# ultra-violet-tooth-sensor-mk-2_0.net
KiCad netlist of a schematic drawn in EAGLE
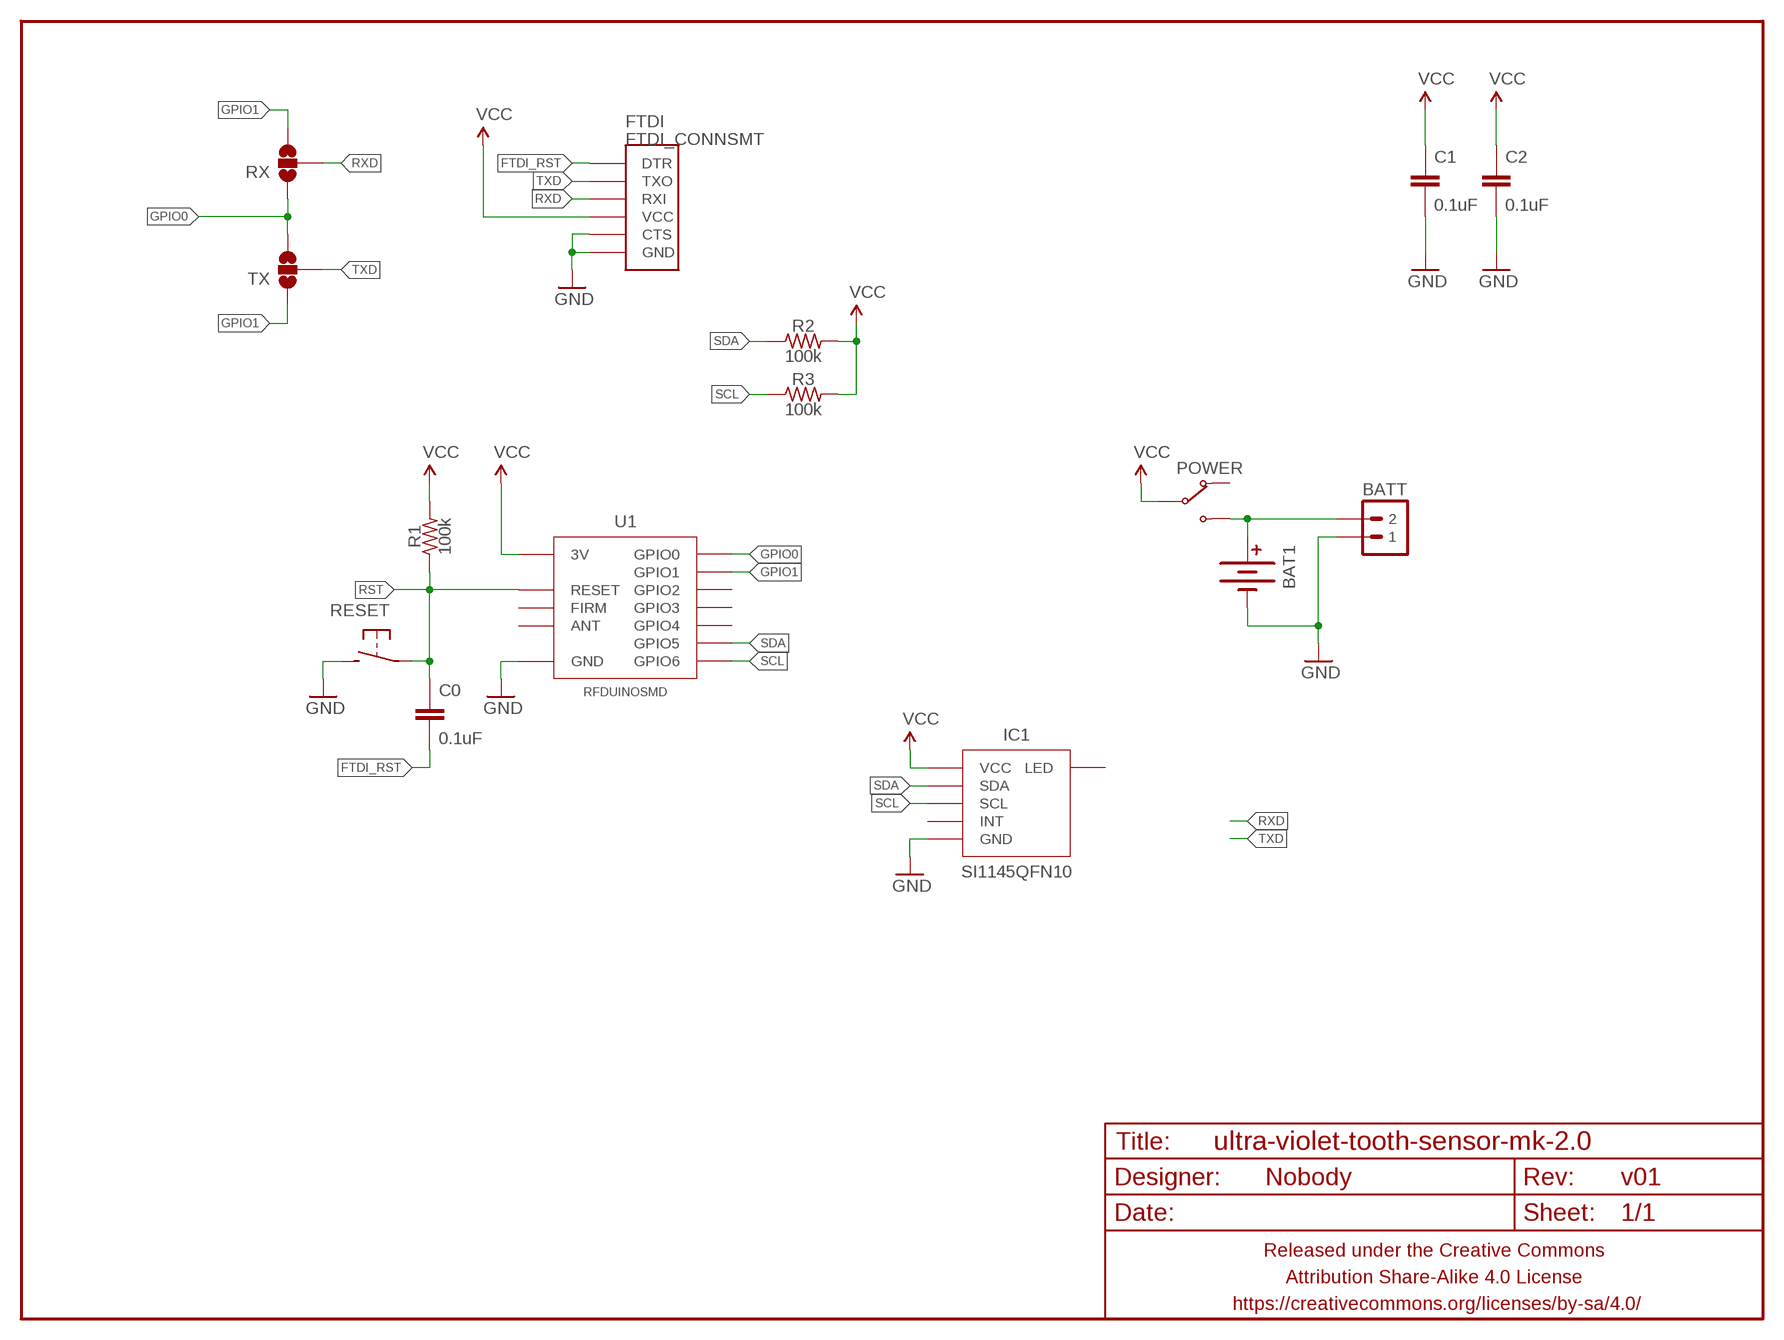
[diagram p0: schematic, sheet 1]

(export (version "E")
  (design (tool "Eeschema 10.0.6"))
  (components
    (comp (ref "BAT1")
      (value "BATTERY20MMSMD-MINE")
      (footprint "eagle-import:BATTCON_20MM_MINE")
      (libsource (lib "eagle-import") (part "BATTERY20MMSMD-MINE"))
    )
    (comp (ref "BATT")
      (value "M02PTH-CENTERED-R+")
      (footprint "eagle-import:1X02-CENTER-R+")
      (libsource (lib "eagle-import") (part "M02PTH-CENTERED-R+"))
    )
    (comp (ref "C0")
      (value "0.1uF")
      (footprint "eagle-import:C0805")
      (libsource (lib "eagle-import") (part "CAPACITOR-CERAMICC0805"))
    )
    (comp (ref "C1")
      (value "0.1uF")
      (footprint "eagle-import:C0805")
      (libsource (lib "eagle-import") (part "CAPACITOR-CERAMICC0805"))
    )
    (comp (ref "C2")
      (value "0.1uF")
      (footprint "eagle-import:C0805")
      (libsource (lib "eagle-import") (part "CAPACITOR-CERAMICC0805"))
    )
    (comp (ref "FRAME1")
      (value "FRAME-LETTERNO_PACKAGE")
      (footprint "eagle-import:DUMMY")
      (fields (field (name "DESIGNER") "Nobody"))
      (libsource (lib "eagle-import") (part "FRAME-LETTERNO_PACKAGE"))
    )
    (comp (ref "FTDI")
      (value "FTDI_CONNSMT")
      (footprint "eagle-import:FTDI_CONN_SMT")
      (libsource (lib "eagle-import") (part "FTDI_CONNSMT"))
    )
    (comp (ref "IC1")
      (value "SI1145QFN10")
      (footprint "eagle-import:SI1145")
      (libsource (lib "eagle-import") (part "SI1145QFN10"))
    )
    (comp (ref "POWER")
      (value "SWITCH-SPDTSMD-RA")
      (footprint "eagle-import:SWITCH-SPDT-SMD-RA")
      (libsource (lib "eagle-import") (part "SWITCH-SPDTSMD-RA"))
    )
    (comp (ref "R1")
      (value "100k")
      (footprint "eagle-import:R0805")
      (libsource (lib "eagle-import") (part "RESISTORR0805"))
    )
    (comp (ref "R2")
      (value "100k")
      (footprint "eagle-import:R0805")
      (libsource (lib "eagle-import") (part "RESISTORR0805"))
    )
    (comp (ref "R3")
      (value "100k")
      (footprint "eagle-import:R0805")
      (libsource (lib "eagle-import") (part "RESISTORR0805"))
    )
    (comp (ref "RESET")
      (value "SPST-NO-TACTSMD-TINY")
      (footprint "eagle-import:TACTILE-SWITCH-SMD")
      (libsource (lib "eagle-import") (part "SPST-NO-TACTSMD-TINY"))
    )
    (comp (ref "RX")
      (value "JUMPER-PAD-3-NOFULL_BOX_SILK")
      (footprint "eagle-import:PAD-JUMPER-3-NO_YES_SILK_FULL_BOX")
      (libsource (lib "eagle-import") (part "JUMPER-PAD-3-NOFULL_BOX_SILK"))
    )
    (comp (ref "TX")
      (value "JUMPER-PAD-3-NOFULL_BOX_SILK")
      (footprint "eagle-import:PAD-JUMPER-3-NO_YES_SILK_FULL_BOX")
      (libsource (lib "eagle-import") (part "JUMPER-PAD-3-NOFULL_BOX_SILK"))
    )
    (comp (ref "U1")
      (value "RFDUINOSMD")
      (footprint "eagle-import:RFDUINO-SMD")
      (libsource (lib "eagle-import") (part "RFDUINOSMD"))
    )
  )
  (nets
    (net (code "1") (name "FTDI_RST") (class "Default")
      (node (ref "C0") (pin "2") (pinfunction "2_2") (pintype "passive"))
      (node (ref "FTDI") (pin "DTR") (pinfunction "DTR_DTR") (pintype "bidirectional"))
    )
    (net (code "2") (name "GND") (class "Default")
      (node (ref "BAT1") (pin "BOTTOM") (pinfunction "-_BOTTOM") (pintype "power_in"))
      (node (ref "BATT") (pin "1") (pinfunction "1_1") (pintype "passive"))
      (node (ref "C1") (pin "2") (pinfunction "2_2") (pintype "passive"))
      (node (ref "C2") (pin "2") (pinfunction "2_2") (pintype "passive"))
      (node (ref "FTDI") (pin "CTS") (pinfunction "CTS_CTS") (pintype "bidirectional"))
      (node (ref "FTDI") (pin "GND") (pinfunction "GND_GND") (pintype "bidirectional"))
      (node (ref "IC1") (pin "GND") (pinfunction "GND_GND") (pintype "bidirectional"))
      (node (ref "RESET") (pin "B@1") (pinfunction "2_B@1") (pintype "passive"))
      (node (ref "RESET") (pin "B@2") (pinfunction "2_B@2") (pintype "passive"))
      (node (ref "U1") (pin "GND@1") (pinfunction "GND_GND@1") (pintype "bidirectional"))
      (node (ref "U1") (pin "GND@2") (pinfunction "GND_GND@2") (pintype "bidirectional"))
      (node (ref "U1") (pin "GND@3") (pinfunction "GND_GND@3") (pintype "bidirectional"))
      (node (ref "U1") (pin "GND@4") (pinfunction "GND_GND@4") (pintype "bidirectional"))
      (node (ref "U1") (pin "GND@5") (pinfunction "GND_GND@5") (pintype "bidirectional"))
      (node (ref "U1") (pin "GND@6") (pinfunction "GND_GND@6") (pintype "bidirectional"))
      (node (ref "U1") (pin "GND@7") (pinfunction "GND_GND@7") (pintype "bidirectional"))
      (node (ref "U1") (pin "GND@8") (pinfunction "GND_GND@8") (pintype "bidirectional"))
    )
    (net (code "3") (name "GPIO0") (class "Default")
      (node (ref "RX") (pin "1") (pinfunction "1_1") (pintype "passive"))
      (node (ref "TX") (pin "3") (pinfunction "3_3") (pintype "passive"))
      (node (ref "U1") (pin "GPIO0") (pinfunction "GPIO0_GPIO0") (pintype "bidirectional"))
    )
    (net (code "4") (name "GPIO1") (class "Default")
      (node (ref "RX") (pin "3") (pinfunction "3_3") (pintype "passive"))
      (node (ref "TX") (pin "1") (pinfunction "1_1") (pintype "passive"))
      (node (ref "U1") (pin "GPIO1") (pinfunction "GPIO1_GPIO1") (pintype "bidirectional"))
    )
    (net (code "5") (name "Net-(POWER-NO)") (class "Default")
      (node (ref "BAT1") (pin "TOP@1") (pinfunction "+_TOP@1") (pintype "power_in"))
      (node (ref "BAT1") (pin "TOP@2") (pinfunction "+_TOP@2") (pintype "power_in"))
      (node (ref "BATT") (pin "2") (pinfunction "2_2") (pintype "passive"))
      (node (ref "POWER") (pin "1") (pinfunction "NO_1") (pintype "passive"))
    )
    (net (code "6") (name "RST") (class "Default")
      (node (ref "C0") (pin "1") (pinfunction "1_1") (pintype "passive"))
      (node (ref "R1") (pin "1") (pinfunction "1_1") (pintype "passive"))
      (node (ref "RESET") (pin "A@1") (pinfunction "1_A@1") (pintype "passive"))
      (node (ref "RESET") (pin "A@2") (pinfunction "1_A@2") (pintype "passive"))
      (node (ref "U1") (pin "RESET") (pinfunction "RESET_RESET") (pintype "bidirectional"))
    )
    (net (code "7") (name "RXD") (class "Default")
      (node (ref "FTDI") (pin "RXI") (pinfunction "RXI_RXI") (pintype "bidirectional"))
      (node (ref "RX") (pin "2") (pinfunction "2_2") (pintype "passive"))
    )
    (net (code "8") (name "SCL") (class "Default")
      (node (ref "IC1") (pin "SCL") (pinfunction "SCL_SCL") (pintype "bidirectional"))
      (node (ref "R3") (pin "1") (pinfunction "1_1") (pintype "passive"))
      (node (ref "U1") (pin "GPIO6") (pinfunction "GPIO6_GPIO6") (pintype "bidirectional"))
    )
    (net (code "9") (name "SDA") (class "Default")
      (node (ref "IC1") (pin "SDA") (pinfunction "SDA_SDA") (pintype "bidirectional"))
      (node (ref "R2") (pin "1") (pinfunction "1_1") (pintype "passive"))
      (node (ref "U1") (pin "GPIO5") (pinfunction "GPIO5_GPIO5") (pintype "bidirectional"))
    )
    (net (code "10") (name "TXD") (class "Default")
      (node (ref "FTDI") (pin "TXO") (pinfunction "TXO_TXO") (pintype "bidirectional"))
      (node (ref "TX") (pin "2") (pinfunction "2_2") (pintype "passive"))
    )
    (net (code "11") (name "VCC") (class "Default")
      (node (ref "C1") (pin "1") (pinfunction "1_1") (pintype "passive"))
      (node (ref "C2") (pin "1") (pinfunction "1_1") (pintype "passive"))
      (node (ref "FTDI") (pin "VCC") (pinfunction "VCC_VCC") (pintype "bidirectional"))
      (node (ref "IC1") (pin "VCC@1") (pinfunction "VCC_VCC@1") (pintype "bidirectional"))
      (node (ref "IC1") (pin "VCC@2") (pinfunction "VCC_VCC@2") (pintype "bidirectional"))
      (node (ref "IC1") (pin "VCC@3") (pinfunction "VCC_VCC@3") (pintype "bidirectional"))
      (node (ref "POWER") (pin "2") (pinfunction "COM_2") (pintype "passive"))
      (node (ref "R1") (pin "2") (pinfunction "2_2") (pintype "passive"))
      (node (ref "R2") (pin "2") (pinfunction "2_2") (pintype "passive"))
      (node (ref "R3") (pin "2") (pinfunction "2_2") (pintype "passive"))
      (node (ref "U1") (pin "3V") (pinfunction "3V_3V") (pintype "bidirectional"))
    )
    (net (code "12") (name "unconnected-(IC1-PadINT)") (class "Default")
      (node (ref "IC1") (pin "INT") (pinfunction "INT_INT") (pintype "bidirectional"))
    )
    (net (code "13") (name "unconnected-(IC1-PadLED)") (class "Default")
      (node (ref "IC1") (pin "LED") (pinfunction "LED_LED") (pintype "bidirectional"))
    )
    (net (code "14") (name "unconnected-(POWER-NC-Pad3)") (class "Default")
      (node (ref "POWER") (pin "3") (pinfunction "NC_3") (pintype "passive"))
    )
    (net (code "15") (name "unconnected-(U1-FIRM-PadFACTORY)") (class "Default")
      (node (ref "U1") (pin "FACTORY") (pinfunction "FIRM_FACTORY") (pintype "bidirectional"))
    )
    (net (code "16") (name "unconnected-(U1-PadANT)") (class "Default")
      (node (ref "U1") (pin "ANT") (pinfunction "ANT_ANT") (pintype "bidirectional"))
    )
    (net (code "17") (name "unconnected-(U1-PadGPIO2)") (class "Default")
      (node (ref "U1") (pin "GPIO2") (pinfunction "GPIO2_GPIO2") (pintype "bidirectional"))
    )
    (net (code "18") (name "unconnected-(U1-PadGPIO3)") (class "Default")
      (node (ref "U1") (pin "GPIO3") (pinfunction "GPIO3_GPIO3") (pintype "bidirectional"))
    )
    (net (code "19") (name "unconnected-(U1-PadGPIO4)") (class "Default")
      (node (ref "U1") (pin "GPIO4") (pinfunction "GPIO4_GPIO4") (pintype "bidirectional"))
    )
  )
)
